# TK-BB-MD-06.net
KiCad netlist of a schematic drawn in EAGLE
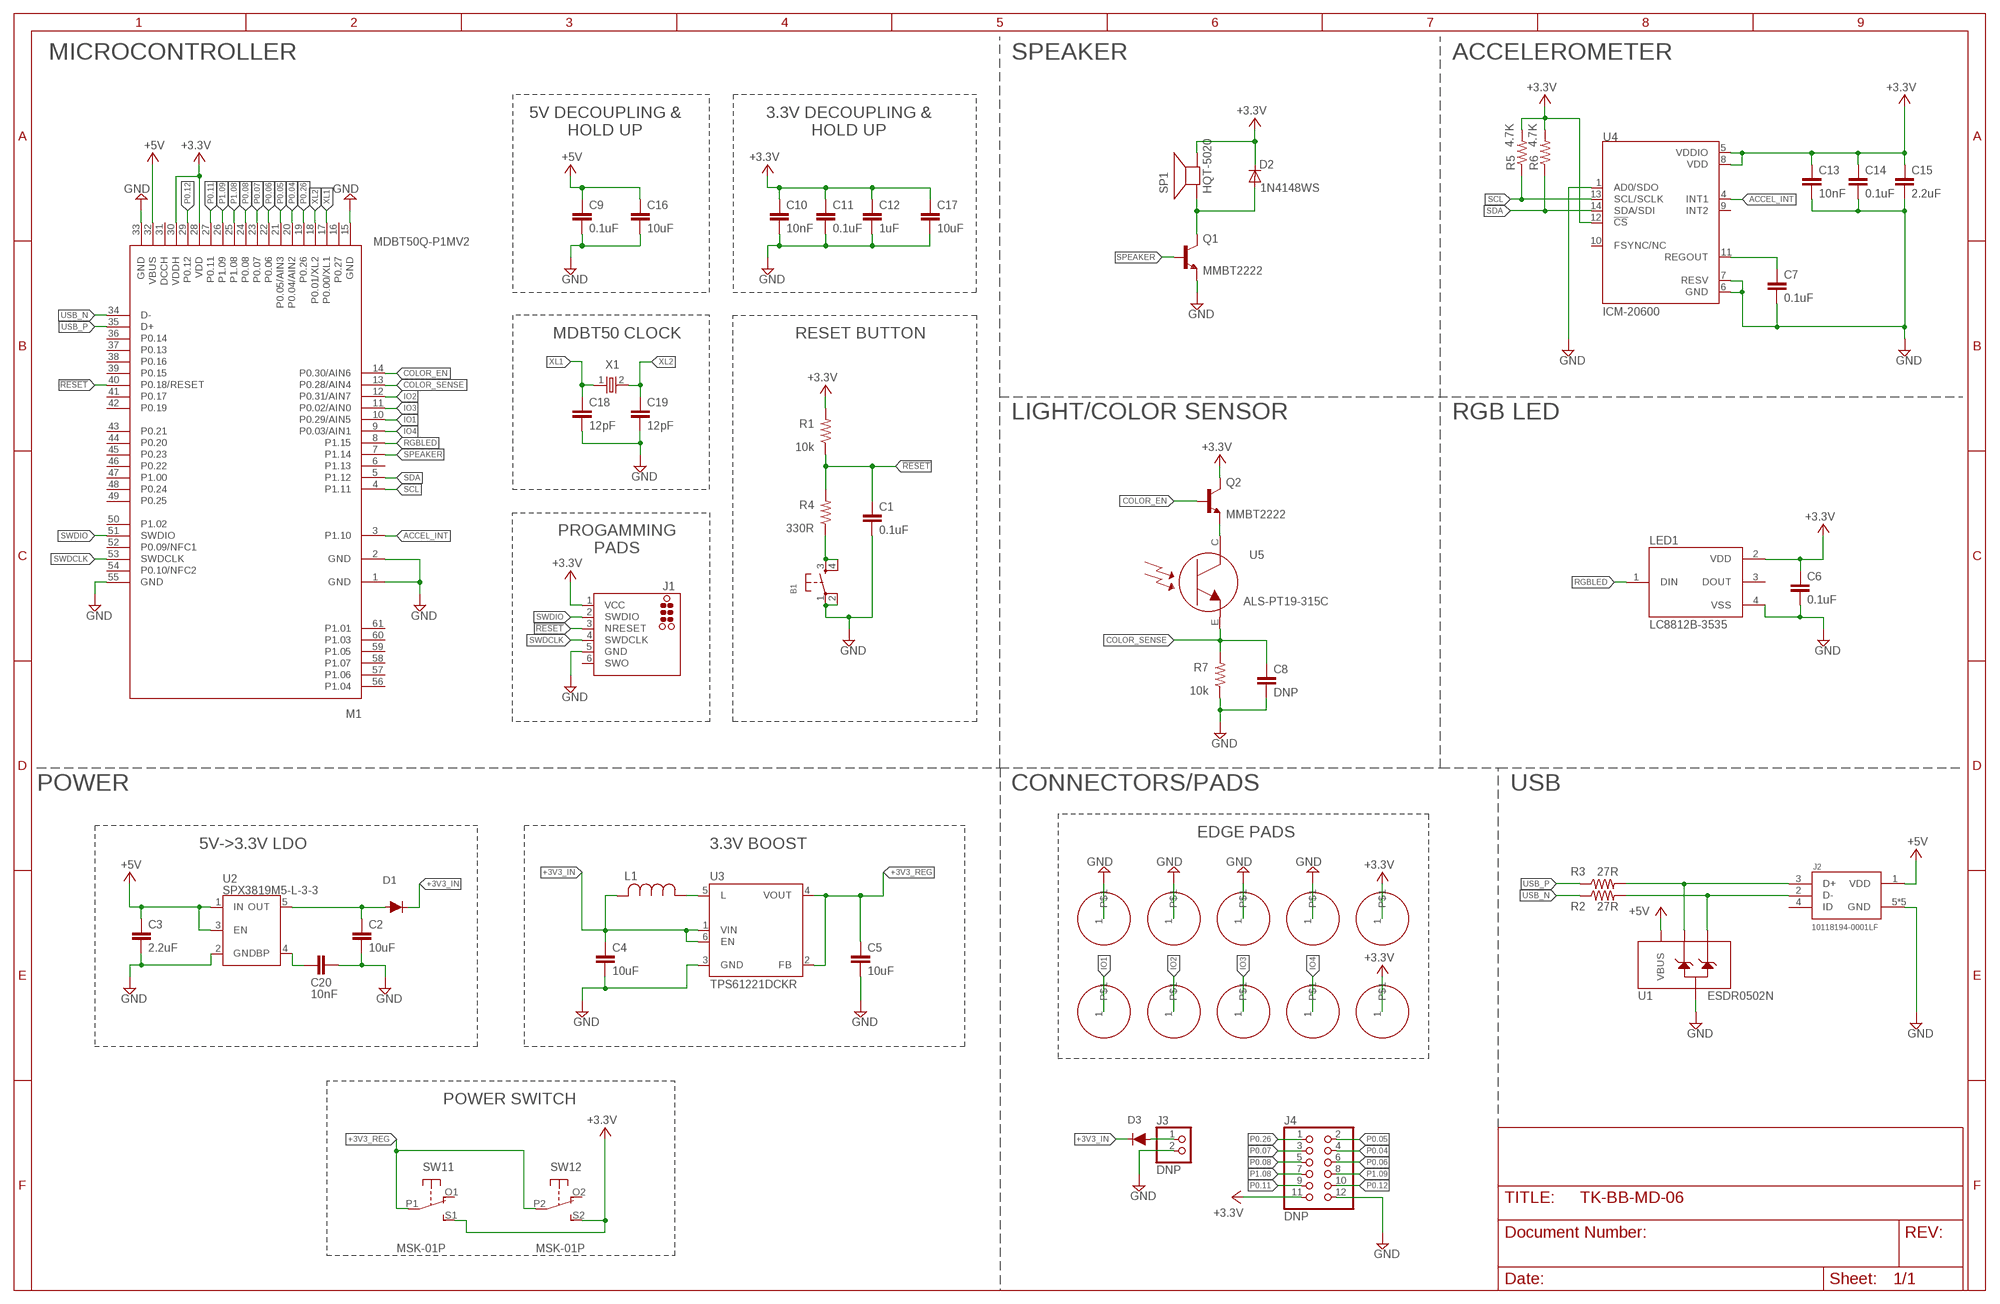
[diagram p0: schematic, sheet 1]

(export (version "E")
  (design (tool "Eeschema 10.0.6"))
  (components
    (comp (ref "B1")
      (value "KFC-A04-02(H3.8)")
      (footprint "eagle-import:KFC-AO4-02")
      (fields (field (name "MANUFACTURER") "Yeuqing City Ouke Electronics"))
      (libsource (lib "eagle-import") (part "BUTTON_SMT_KFC-A04-02_3.8MMH"))
    )
    (comp (ref "C1")
      (value "0.1uF")
      (footprint "eagle-import:0402")
      (fields
        (field (name "MANUFACTURER") "Yageo")
        (field (name "MANUFACTURER_PART_NUMBER") "CC0402KRX7R6BB104")
      )
      (libsource (lib "eagle-import") (part "C_0402_0.1UF_10V"))
    )
    (comp (ref "C2")
      (value "10uF")
      (footprint "eagle-import:0402")
      (fields
        (field (name "MANUFACTURER") "Samsung")
        (field (name "MANUFACTURER_PART_NUMBER") "CL05A106MP8NUB8")
      )
      (libsource (lib "eagle-import") (part "C_0402_10UF_10V"))
    )
    (comp (ref "C3")
      (value "2.2uF")
      (footprint "eagle-import:0402")
      (fields
        (field (name "MANUFACTURER") "Taiyo Yuden")
        (field (name "MANUFACTURER_PART_NUMBER") "LMK105BJ225MV-F")
      )
      (libsource (lib "eagle-import") (part "C_0402_2.2UF_10V"))
    )
    (comp (ref "C4")
      (value "10uF")
      (footprint "eagle-import:0402")
      (fields
        (field (name "MANUFACTURER") "Samsung")
        (field (name "MANUFACTURER_PART_NUMBER") "CL05A106MP8NUB8")
      )
      (libsource (lib "eagle-import") (part "C_0402_10UF_10V"))
    )
    (comp (ref "C5")
      (value "10uF")
      (footprint "eagle-import:0402")
      (fields
        (field (name "MANUFACTURER") "Samsung")
        (field (name "MANUFACTURER_PART_NUMBER") "CL05A106MP8NUB8")
      )
      (libsource (lib "eagle-import") (part "C_0402_10UF_10V"))
    )
    (comp (ref "C6")
      (value "0.1uF")
      (footprint "eagle-import:0402")
      (fields
        (field (name "MANUFACTURER") "Yageo")
        (field (name "MANUFACTURER_PART_NUMBER") "CC0402KRX7R6BB104")
      )
      (libsource (lib "eagle-import") (part "C_0402_0.1UF_10V"))
    )
    (comp (ref "C7")
      (value "0.1uF")
      (footprint "eagle-import:0402")
      (fields
        (field (name "MANUFACTURER") "Yageo")
        (field (name "MANUFACTURER_PART_NUMBER") "CC0402KRX7R6BB104")
      )
      (libsource (lib "eagle-import") (part "C_0402_0.1UF_10V"))
    )
    (comp (ref "C8")
      (value "DNP")
      (footprint "eagle-import:0402")
      (libsource (lib "eagle-import") (part "C_0402_DNP"))
    )
    (comp (ref "C9")
      (value "0.1uF")
      (footprint "eagle-import:0402")
      (fields
        (field (name "MANUFACTURER") "Yageo")
        (field (name "MANUFACTURER_PART_NUMBER") "CC0402KRX7R6BB104")
      )
      (libsource (lib "eagle-import") (part "C_0402_0.1UF_10V"))
    )
    (comp (ref "C10")
      (value "10nF")
      (footprint "eagle-import:0402")
      (fields
        (field (name "MANUFACTURER") "Yageo")
        (field (name "MANUFACTURER_PART_NUMBER") "C0402C103K8RACTU")
      )
      (libsource (lib "eagle-import") (part "C_0402_10NF_10V"))
    )
    (comp (ref "C11")
      (value "0.1uF")
      (footprint "eagle-import:0402")
      (fields
        (field (name "MANUFACTURER") "Yageo")
        (field (name "MANUFACTURER_PART_NUMBER") "CC0402KRX7R6BB104")
      )
      (libsource (lib "eagle-import") (part "C_0402_0.1UF_10V"))
    )
    (comp (ref "C12")
      (value "1uF")
      (footprint "eagle-import:0402")
      (fields
        (field (name "MANUFACTURER") "Yageo")
        (field (name "MANUFACTURER_PART_NUMBER") "CC0402KRX5R6BB105")
      )
      (libsource (lib "eagle-import") (part "C_0402_1UF_10V"))
    )
    (comp (ref "C13")
      (value "10nF")
      (footprint "eagle-import:0402")
      (fields
        (field (name "MANUFACTURER") "Yageo")
        (field (name "MANUFACTURER_PART_NUMBER") "C0402C103K8RACTU")
      )
      (libsource (lib "eagle-import") (part "C_0402_10NF_10V"))
    )
    (comp (ref "C14")
      (value "0.1uF")
      (footprint "eagle-import:0402")
      (fields
        (field (name "MANUFACTURER") "Yageo")
        (field (name "MANUFACTURER_PART_NUMBER") "CC0402KRX7R6BB104")
      )
      (libsource (lib "eagle-import") (part "C_0402_0.1UF_10V"))
    )
    (comp (ref "C15")
      (value "2.2uF")
      (footprint "eagle-import:0402")
      (fields
        (field (name "MANUFACTURER") "Taiyo Yuden")
        (field (name "MANUFACTURER_PART_NUMBER") "LMK105BJ225MV-F")
      )
      (libsource (lib "eagle-import") (part "C_0402_2.2UF_10V"))
    )
    (comp (ref "C16")
      (value "10uF")
      (footprint "eagle-import:0402")
      (fields
        (field (name "MANUFACTURER") "Samsung")
        (field (name "MANUFACTURER_PART_NUMBER") "CL05A106MP8NUB8")
      )
      (libsource (lib "eagle-import") (part "C_0402_10UF_10V"))
    )
    (comp (ref "C17")
      (value "10uF")
      (footprint "eagle-import:0402")
      (fields
        (field (name "MANUFACTURER") "Samsung")
        (field (name "MANUFACTURER_PART_NUMBER") "CL05A106MP8NUB8")
      )
      (libsource (lib "eagle-import") (part "C_0402_10UF_10V"))
    )
    (comp (ref "C18")
      (value "12pF")
      (footprint "eagle-import:0402")
      (fields
        (field (name "MANUFACTURER") "TDK Corporation")
        (field (name "MANUFACTURER_PART_NUMBER") "CGA2B2C0G1H120J050BA")
      )
      (libsource (lib "eagle-import") (part "C_0402_12PF_50V"))
    )
    (comp (ref "C19")
      (value "12pF")
      (footprint "eagle-import:0402")
      (fields
        (field (name "MANUFACTURER") "TDK Corporation")
        (field (name "MANUFACTURER_PART_NUMBER") "CGA2B2C0G1H120J050BA")
      )
      (libsource (lib "eagle-import") (part "C_0402_12PF_50V"))
    )
    (comp (ref "C20")
      (value "10nF")
      (footprint "eagle-import:0402")
      (fields
        (field (name "MANUFACTURER") "Yageo")
        (field (name "MANUFACTURER_PART_NUMBER") "C0402C103K8RACTU")
      )
      (libsource (lib "eagle-import") (part "C_0402_10NF_10V"))
    )
    (comp (ref "D1")
      (value "NSR0320MW2T1G")
      (footprint "eagle-import:SOD323")
      (fields (field (name "MANUFACTURER") "ON Semiconductor"))
      (libsource (lib "eagle-import") (part "DIODE_SCHOTTKY_NSR0320MW2T1G"))
    )
    (comp (ref "D2")
      (value "1N4148WS")
      (footprint "eagle-import:SOD-323")
      (fields (field (name "MANUFACTURER") "ON Semiconductor"))
      (libsource (lib "eagle-import") (part "DIODESOD-323_1N148WS"))
    )
    (comp (ref "D3")
      (value "NSR0320MW2T1G")
      (footprint "eagle-import:SOD323")
      (fields (field (name "MANUFACTURER") "ON Semiconductor"))
      (libsource (lib "eagle-import") (part "DIODE_SCHOTTKY_NSR0320MW2T1G"))
    )
    (comp (ref "J1")
      (value "DNP")
      (footprint "eagle-import:TC2030-MCP-NL")
      (libsource (lib "eagle-import") (part "TC2030-MCP-NL"))
    )
    (comp (ref "J2")
      (value "10118194-0001LF")
      (footprint "eagle-import:10118194-0001LF")
      (fields (field (name "MANUFACTURER") "Amphenol"))
      (libsource (lib "eagle-import") (part "10118194-0001LF"))
    )
    (comp (ref "J3")
      (value "DNP")
      (footprint "eagle-import:1X02")
      (fields
        (field (name "MANUFACTURER") "Amphenol")
        (field (name "MANUFACTURER_PART_NUMBER") "68000-402HLF")
      )
      (libsource (lib "eagle-import") (part "PINHD-1X2"))
    )
    (comp (ref "J4")
      (value "DNP")
      (footprint "eagle-import:2X06")
      (fields
        (field (name "MANUFACTURER") "Amphenol")
        (field (name "MANUFACTURER_PART_NUMBER") "67997-412HLF")
      )
      (libsource (lib "eagle-import") (part "PINHD-2X6"))
    )
    (comp (ref "L1")
      (value "4.7uH")
      (footprint "eagle-import:SRN30104R7M_IND_BOURNS_SRN3010")
      (fields
        (field (name "MANUFACTURER") "Bourns Electronics")
        (field (name "MANUFACTURER_PART_NUMBER") "SRN30104R7M")
      )
      (libsource (lib "eagle-import") (part "SRN30104R7M_SRN3010-4R7M"))
    )
    (comp (ref "LED1")
      (value "LC8812B-3535")
      (footprint "eagle-import:LC8812B-3535")
      (libsource (lib "eagle-import") (part "SK6812MINI_LC8812B-3535"))
    )
    (comp (ref "M1")
      (value "MDBT50Q-P1MV2")
      (footprint "eagle-import:MDBT50")
      (fields (field (name "MANUFACTURER") "Raytac"))
      (libsource (lib "eagle-import") (part "MDBT50Q-P1MV2"))
    )
    (comp (ref "P1")
      (value "BB_CHICKLET_PADS_ROUND")
      (footprint "eagle-import:BB_CHICKLET_PAD")
      (libsource (lib "eagle-import") (part "BB_CHICKLET_PADS_ROUND"))
    )
    (comp (ref "P2")
      (value "BB_CHICKLET_PADS_ROUND")
      (footprint "eagle-import:BB_CHICKLET_PAD")
      (libsource (lib "eagle-import") (part "BB_CHICKLET_PADS_ROUND"))
    )
    (comp (ref "P3")
      (value "BB_CHICKLET_PADS_ROUND")
      (footprint "eagle-import:BB_CHICKLET_PAD")
      (libsource (lib "eagle-import") (part "BB_CHICKLET_PADS_ROUND"))
    )
    (comp (ref "P4")
      (value "BB_CHICKLET_PADS_ROUND")
      (footprint "eagle-import:BB_CHICKLET_PAD")
      (libsource (lib "eagle-import") (part "BB_CHICKLET_PADS_ROUND"))
    )
    (comp (ref "P5")
      (value "BB_CHICKLET_PADS_ROUND")
      (footprint "eagle-import:BB_CHICKLET_PAD")
      (libsource (lib "eagle-import") (part "BB_CHICKLET_PADS_ROUND"))
    )
    (comp (ref "P6")
      (value "BB_CHICKLET_PADS_ROUND")
      (footprint "eagle-import:BB_CHICKLET_PAD")
      (libsource (lib "eagle-import") (part "BB_CHICKLET_PADS_ROUND"))
    )
    (comp (ref "P7")
      (value "BB_CHICKLET_PADS_ROUND")
      (footprint "eagle-import:BB_CHICKLET_PAD")
      (libsource (lib "eagle-import") (part "BB_CHICKLET_PADS_ROUND"))
    )
    (comp (ref "P8")
      (value "BB_CHICKLET_PADS_ROUND")
      (footprint "eagle-import:BB_CHICKLET_PAD")
      (libsource (lib "eagle-import") (part "BB_CHICKLET_PADS_ROUND"))
    )
    (comp (ref "P9")
      (value "BB_CHICKLET_PADS_ROUND")
      (footprint "eagle-import:BB_CHICKLET_PAD")
      (libsource (lib "eagle-import") (part "BB_CHICKLET_PADS_ROUND"))
    )
    (comp (ref "P10")
      (value "BB_CHICKLET_PADS_ROUND")
      (footprint "eagle-import:BB_CHICKLET_PAD")
      (libsource (lib "eagle-import") (part "BB_CHICKLET_PADS_ROUND"))
    )
    (comp (ref "Q1")
      (value "MMBT2222")
      (footprint "eagle-import:SOT23-WIDE")
      (fields
        (field (name "MANUFACTURER") "ON Semiconductor")
        (field (name "MANUFACTURER_PART_NUMBER") "MMBT2222LT1G")
      )
      (libsource (lib "eagle-import") (part "TRANSISTOR_NPN_WIDE_MMBT2222"))
    )
    (comp (ref "Q2")
      (value "MMBT2222")
      (footprint "eagle-import:SOT23-WIDE")
      (fields
        (field (name "MANUFACTURER") "ON Semiconductor")
        (field (name "MANUFACTURER_PART_NUMBER") "MMBT2222LT1G")
      )
      (libsource (lib "eagle-import") (part "TRANSISTOR_NPN_WIDE_MMBT2222"))
    )
    (comp (ref "R1")
      (value "10k")
      (footprint "eagle-import:0402")
      (fields
        (field (name "MANUFACTURER") "Yageo")
        (field (name "MANUFACTURER_PART_NUMBER") "RC0402JR-0710KL")
      )
      (libsource (lib "eagle-import") (part "R_0402_10K_0.0625W"))
    )
    (comp (ref "R2")
      (value "27R")
      (footprint "eagle-import:0402")
      (fields
        (field (name "MANUFACTURER") "Yageo")
        (field (name "MANUFACTURER_PART_NUMBER") "AC0402FR-0727RL")
      )
      (libsource (lib "eagle-import") (part "R_0402_27R_0.0625W"))
    )
    (comp (ref "R3")
      (value "27R")
      (footprint "eagle-import:0402")
      (fields
        (field (name "MANUFACTURER") "Yageo")
        (field (name "MANUFACTURER_PART_NUMBER") "AC0402FR-0727RL")
      )
      (libsource (lib "eagle-import") (part "R_0402_27R_0.0625W"))
    )
    (comp (ref "R4")
      (value "330R")
      (footprint "eagle-import:0402")
      (fields
        (field (name "MANUFACTURER") "Yageo")
        (field (name "MANUFACTURER_PART_NUMBER") "RC0402JR-07330RL")
      )
      (libsource (lib "eagle-import") (part "R_0402_330R_0.0625W"))
    )
    (comp (ref "R5")
      (value "4.7K")
      (footprint "eagle-import:0402")
      (fields
        (field (name "MANUFACTURER") "Yageo")
        (field (name "MANUFACTURER_PART_NUMBER") "RC0402JR-074K7L")
      )
      (libsource (lib "eagle-import") (part "R_0402_4.7K_0.0625W"))
    )
    (comp (ref "R6")
      (value "4.7K")
      (footprint "eagle-import:0402")
      (fields
        (field (name "MANUFACTURER") "Yageo")
        (field (name "MANUFACTURER_PART_NUMBER") "RC0402JR-074K7L")
      )
      (libsource (lib "eagle-import") (part "R_0402_4.7K_0.0625W"))
    )
    (comp (ref "R7")
      (value "10k")
      (footprint "eagle-import:0402")
      (fields
        (field (name "MANUFACTURER") "Panasonic")
        (field (name "MANUFACTURER_PART_NUMBER") "ERJ-2GEJ103X")
      )
      (libsource (lib "eagle-import") (part "R_0402_10K_0.1W"))
    )
    (comp (ref "SP1")
      (value "HQT-5020")
      (footprint "eagle-import:HQT-5020")
      (libsource (lib "eagle-import") (part "SPEAKER_HQT-5020"))
    )
    (comp (ref "SW1")
      (value "MSK-01P")
      (footprint "eagle-import:MSK-01P")
      (fields (field (name "MANUFACTURER") "Shenzen Gangyuan Microkey Technology"))
      (libsource (lib "eagle-import") (part "DPDT_MSK-01P"))
    )
    (comp (ref "U1")
      (value "ESDR0502N")
      (footprint "eagle-import:6-UFDFN")
      (fields
        (field (name "MANUFACTURER") "ON Semiconductor")
        (field (name "MANUFACTURER_PART_NUMBER") "ESDR0502NMUTBG")
      )
      (libsource (lib "eagle-import") (part "ESDR0502N"))
    )
    (comp (ref "U2")
      (value "SPX3819M5-L-3-3")
      (footprint "eagle-import:SOT23-5")
      (fields (field (name "MANUFACTURER") "MaxLinear"))
      (libsource (lib "eagle-import") (part "SPX3819_3.3V"))
    )
    (comp (ref "U3")
      (value "TPS61221DCKR")
      (footprint "eagle-import:SC70-6")
      (fields (field (name "MANUFACTURER") "Texas Instruments"))
      (libsource (lib "eagle-import") (part "TPS61221"))
    )
    (comp (ref "U4")
      (value "ICM-20600")
      (footprint "eagle-import:ICM-20600")
      (fields (field (name "MANUFACTURER") "TDK-InvenSense"))
      (libsource (lib "eagle-import") (part "ICM-20600"))
    )
    (comp (ref "U5")
      (value "ALS-PT19-315C")
      (footprint "eagle-import:ALS-PT19-315C")
      (fields
        (field (name "MANUFACTURER") "Everlight Electronics Co Ltd")
        (field (name "MANUFACTURER_PART_NUMBER") "ALS-PT19-315C/L177/TR8")
      )
      (libsource (lib "eagle-import") (part "ALS-PT19-315C"))
    )
    (comp (ref "X1")
      (value "32kHz 9pF")
      (footprint "eagle-import:XTAL_3215_N")
      (description "CRYSTAL 32.7680KHZ 9PF SMD")
      (fields
        (field (name "MANUFACTURER") "EPSON")
        (field (name "MANUFACTURER_PART_NUMBER") "FC-135 32.7680KA-AC0")
        (field (name "MANUFACTURER_1") "ECS Inc.")
        (field (name "MANUFACTURER_PART_NUMBER_1") "ECS-.327-9-34B-TR")
      )
      (libsource (lib "eagle-import") (part "XTAL_32KHZ_9PF"))
    )
  )
  (nets
    (net (code "1") (name "+3.3V") (class "Default")
      (node (ref "C10") (pin "1") (pinfunction "1_1") (pintype "passive"))
      (node (ref "C11") (pin "1") (pinfunction "1_1") (pintype "passive"))
      (node (ref "C12") (pin "1") (pinfunction "1_1") (pintype "passive"))
      (node (ref "C13") (pin "1") (pinfunction "1_1") (pintype "passive"))
      (node (ref "C14") (pin "1") (pinfunction "1_1") (pintype "passive"))
      (node (ref "C15") (pin "1") (pinfunction "1_1") (pintype "passive"))
      (node (ref "C17") (pin "1") (pinfunction "1_1") (pintype "passive"))
      (node (ref "C6") (pin "1") (pinfunction "1_1") (pintype "passive"))
      (node (ref "D2") (pin "C") (pinfunction "C_C") (pintype "passive"))
      (node (ref "J1") (pin "1") (pinfunction "VCC_1") (pintype "passive"))
      (node (ref "J4") (pin "11") (pinfunction "11_11") (pintype "passive"))
      (node (ref "LED1") (pin "2") (pinfunction "VDD_2") (pintype "power_in"))
      (node (ref "M1") (pin "28") (pinfunction "VDD_28") (pintype "bidirectional"))
      (node (ref "M1") (pin "30") (pinfunction "VDDH_30") (pintype "bidirectional"))
      (node (ref "P10") (pin "1") (pinfunction "P$1_1") (pintype "bidirectional"))
      (node (ref "P9") (pin "1") (pinfunction "P$1_1") (pintype "bidirectional"))
      (node (ref "Q2") (pin "3") (pinfunction "C_3") (pintype "passive"))
      (node (ref "R1") (pin "2") (pinfunction "2_2") (pintype "passive"))
      (node (ref "R5") (pin "2") (pinfunction "2_2") (pintype "passive"))
      (node (ref "R6") (pin "2") (pinfunction "2_2") (pintype "passive"))
      (node (ref "SP1") (pin "-") (pinfunction "-_-") (pintype "passive"))
      (node (ref "SW1") (pin "S1") (pinfunction "S_S1") (pintype "passive"))
      (node (ref "SW1") (pin "S2") (pinfunction "S_S2") (pintype "passive"))
      (node (ref "U4") (pin "12") (pinfunction "~{CS}_12") (pintype "input"))
      (node (ref "U4") (pin "5") (pinfunction "VDDIO_5") (pintype "power_in"))
      (node (ref "U4") (pin "8") (pinfunction "VDD_8") (pintype "power_in"))
    )
    (net (code "2") (name "+3V3_IN") (class "Default")
      (node (ref "C4") (pin "1") (pinfunction "1_1") (pintype "passive"))
      (node (ref "D1") (pin "1") (pinfunction "C_1") (pintype "bidirectional"))
      (node (ref "D3") (pin "1") (pinfunction "C_1") (pintype "bidirectional"))
      (node (ref "L1") (pin "2") (pinfunction "2_2") (pintype "passive"))
      (node (ref "U3") (pin "1") (pinfunction "VIN_1") (pintype "bidirectional"))
      (node (ref "U3") (pin "6") (pinfunction "EN_6") (pintype "bidirectional"))
    )
    (net (code "3") (name "+3V3_REG") (class "Default")
      (node (ref "C5") (pin "1") (pinfunction "1_1") (pintype "passive"))
      (node (ref "SW1") (pin "P1") (pinfunction "P_P1") (pintype "passive"))
      (node (ref "SW1") (pin "P2") (pinfunction "P_P2") (pintype "passive"))
      (node (ref "U3") (pin "2") (pinfunction "FB_2") (pintype "bidirectional"))
      (node (ref "U3") (pin "4") (pinfunction "VOUT_4") (pintype "bidirectional"))
    )
    (net (code "4") (name "+5V") (class "Default")
      (node (ref "C16") (pin "1") (pinfunction "1_1") (pintype "passive"))
      (node (ref "C3") (pin "1") (pinfunction "1_1") (pintype "passive"))
      (node (ref "C9") (pin "1") (pinfunction "1_1") (pintype "passive"))
      (node (ref "J2") (pin "1") (pinfunction "VDD_1") (pintype "power_in"))
      (node (ref "M1") (pin "32") (pinfunction "VBUS_32") (pintype "bidirectional"))
      (node (ref "U1") (pin "P$6") (pinfunction "VBUS_P$6") (pintype "bidirectional"))
      (node (ref "U2") (pin "1") (pinfunction "IN_1") (pintype "input"))
      (node (ref "U2") (pin "3") (pinfunction "EN_3") (pintype "input"))
    )
    (net (code "5") (name "/~{RESET}") (class "Default")
      (node (ref "C1") (pin "1") (pinfunction "1_1") (pintype "passive"))
      (node (ref "J1") (pin "3") (pinfunction "NRESET_3") (pintype "power_in"))
      (node (ref "M1") (pin "40") (pinfunction "P0.18/RESET_40") (pintype "bidirectional"))
      (node (ref "R1") (pin "1") (pinfunction "1_1") (pintype "passive"))
      (node (ref "R4") (pin "2") (pinfunction "2_2") (pintype "passive"))
    )
    (net (code "6") (name "ACCEL_INT") (class "Default")
      (node (ref "M1") (pin "3") (pinfunction "P1.10_3") (pintype "bidirectional"))
      (node (ref "U4") (pin "4") (pinfunction "INT1_4") (pintype "output"))
    )
    (net (code "7") (name "COLOR_EN") (class "Default")
      (node (ref "M1") (pin "14") (pinfunction "P0.30/AIN6_14") (pintype "bidirectional"))
      (node (ref "Q2") (pin "1") (pinfunction "B_1") (pintype "passive"))
    )
    (net (code "8") (name "COLOR_SENSE") (class "Default")
      (node (ref "C8") (pin "1") (pinfunction "1_1") (pintype "passive"))
      (node (ref "M1") (pin "13") (pinfunction "P0.28/AIN4_13") (pintype "bidirectional"))
      (node (ref "R7") (pin "2") (pinfunction "2_2") (pintype "passive"))
      (node (ref "U5") (pin "E") (pinfunction "E_E") (pintype "bidirectional"))
    )
    (net (code "9") (name "GND") (class "Default")
      (node (ref "B1") (pin "1") (pinfunction "P_1") (pintype "passive"))
      (node (ref "B1") (pin "2") (pinfunction "P1_2") (pintype "passive"))
      (node (ref "C1") (pin "2") (pinfunction "2_2") (pintype "passive"))
      (node (ref "C10") (pin "2") (pinfunction "2_2") (pintype "passive"))
      (node (ref "C11") (pin "2") (pinfunction "2_2") (pintype "passive"))
      (node (ref "C12") (pin "2") (pinfunction "2_2") (pintype "passive"))
      (node (ref "C13") (pin "2") (pinfunction "2_2") (pintype "passive"))
      (node (ref "C14") (pin "2") (pinfunction "2_2") (pintype "passive"))
      (node (ref "C15") (pin "2") (pinfunction "2_2") (pintype "passive"))
      (node (ref "C16") (pin "2") (pinfunction "2_2") (pintype "passive"))
      (node (ref "C17") (pin "2") (pinfunction "2_2") (pintype "passive"))
      (node (ref "C18") (pin "2") (pinfunction "2_2") (pintype "passive"))
      (node (ref "C19") (pin "2") (pinfunction "2_2") (pintype "passive"))
      (node (ref "C2") (pin "2") (pinfunction "2_2") (pintype "passive"))
      (node (ref "C20") (pin "2") (pinfunction "2_2") (pintype "passive"))
      (node (ref "C3") (pin "2") (pinfunction "2_2") (pintype "passive"))
      (node (ref "C4") (pin "2") (pinfunction "2_2") (pintype "passive"))
      (node (ref "C5") (pin "2") (pinfunction "2_2") (pintype "passive"))
      (node (ref "C6") (pin "2") (pinfunction "2_2") (pintype "passive"))
      (node (ref "C7") (pin "2") (pinfunction "2_2") (pintype "passive"))
      (node (ref "C8") (pin "2") (pinfunction "2_2") (pintype "passive"))
      (node (ref "C9") (pin "2") (pinfunction "2_2") (pintype "passive"))
      (node (ref "J1") (pin "5") (pinfunction "GND_5") (pintype "output"))
      (node (ref "J2") (pin "5") (pinfunction "GND_5") (pintype "power_in"))
      (node (ref "J2") (pin "P$6") (pinfunction "GND_P$6") (pintype "power_in"))
      (node (ref "J2") (pin "P$7") (pinfunction "GND_P$7") (pintype "power_in"))
      (node (ref "J2") (pin "P$8") (pinfunction "GND_P$8") (pintype "power_in"))
      (node (ref "J2") (pin "P$9") (pinfunction "GND_P$9") (pintype "power_in"))
      (node (ref "J3") (pin "2") (pinfunction "2_2") (pintype "passive"))
      (node (ref "J4") (pin "12") (pinfunction "12_12") (pintype "passive"))
      (node (ref "LED1") (pin "4") (pinfunction "VSS_4") (pintype "power_in"))
      (node (ref "M1") (pin "1") (pinfunction "GND_1") (pintype "bidirectional"))
      (node (ref "M1") (pin "15") (pinfunction "GND_15") (pintype "bidirectional"))
      (node (ref "M1") (pin "2") (pinfunction "GND_2") (pintype "bidirectional"))
      (node (ref "M1") (pin "33") (pinfunction "GND_33") (pintype "bidirectional"))
      (node (ref "M1") (pin "55") (pinfunction "GND_55") (pintype "bidirectional"))
      (node (ref "P1") (pin "1") (pinfunction "P$1_1") (pintype "bidirectional"))
      (node (ref "P2") (pin "1") (pinfunction "P$1_1") (pintype "bidirectional"))
      (node (ref "P3") (pin "1") (pinfunction "P$1_1") (pintype "bidirectional"))
      (node (ref "P8") (pin "1") (pinfunction "P$1_1") (pintype "bidirectional"))
      (node (ref "Q1") (pin "2") (pinfunction "E_2") (pintype "passive"))
      (node (ref "R7") (pin "1") (pinfunction "1_1") (pintype "passive"))
      (node (ref "U1") (pin "P$1") (pinfunction "GND_P$1") (pintype "bidirectional"))
      (node (ref "U2") (pin "2") (pinfunction "GND_2") (pintype "input"))
      (node (ref "U3") (pin "3") (pinfunction "GND_3") (pintype "bidirectional"))
      (node (ref "U4") (pin "1") (pinfunction "AD0/SDO_1") (pintype "output"))
      (node (ref "U4") (pin "6") (pinfunction "GND_6") (pintype "power_in"))
      (node (ref "U4") (pin "7") (pinfunction "RESV_7") (pintype "power_in"))
    )
    (net (code "10") (name "IO1") (class "Default")
      (node (ref "M1") (pin "10") (pinfunction "P0.29/AIN5_10") (pintype "bidirectional"))
      (node (ref "P6") (pin "1") (pinfunction "P$1_1") (pintype "bidirectional"))
    )
    (net (code "11") (name "IO2") (class "Default")
      (node (ref "M1") (pin "12") (pinfunction "P0.31/AIN7_12") (pintype "bidirectional"))
      (node (ref "P4") (pin "1") (pinfunction "P$1_1") (pintype "bidirectional"))
    )
    (net (code "12") (name "IO3") (class "Default")
      (node (ref "M1") (pin "11") (pinfunction "P0.02/AIN0_11") (pintype "bidirectional"))
      (node (ref "P7") (pin "1") (pinfunction "P$1_1") (pintype "bidirectional"))
    )
    (net (code "13") (name "IO4") (class "Default")
      (node (ref "M1") (pin "9") (pinfunction "P0.03/AIN1_9") (pintype "bidirectional"))
      (node (ref "P5") (pin "1") (pinfunction "P$1_1") (pintype "bidirectional"))
    )
    (net (code "14") (name "Net-(B1-S)") (class "Default")
      (node (ref "B1") (pin "3") (pinfunction "S_3") (pintype "passive"))
      (node (ref "B1") (pin "4") (pinfunction "S1_4") (pintype "passive"))
      (node (ref "R4") (pin "1") (pinfunction "1_1") (pintype "passive"))
    )
    (net (code "15") (name "Net-(D1-A)") (class "Default")
      (node (ref "C2") (pin "1") (pinfunction "1_1") (pintype "passive"))
      (node (ref "D1") (pin "2") (pinfunction "A_2") (pintype "bidirectional"))
      (node (ref "U2") (pin "5") (pinfunction "OUT_5") (pintype "passive"))
    )
    (net (code "16") (name "Net-(D3-A)") (class "Default")
      (node (ref "D3") (pin "2") (pinfunction "A_2") (pintype "bidirectional"))
      (node (ref "J3") (pin "1") (pinfunction "1_1") (pintype "passive"))
    )
    (net (code "17") (name "Net-(J2-D+)") (class "Default")
      (node (ref "J2") (pin "3") (pinfunction "D+_3") (pintype "bidirectional"))
      (node (ref "R3") (pin "2") (pinfunction "2_2") (pintype "passive"))
      (node (ref "U1") (pin "P$2") (pinfunction "D+_P$2") (pintype "bidirectional"))
      (node (ref "U1") (pin "P$5") (pinfunction "D+_P$5") (pintype "bidirectional"))
    )
    (net (code "18") (name "Net-(J2-D-)") (class "Default")
      (node (ref "J2") (pin "2") (pinfunction "D-_2") (pintype "bidirectional"))
      (node (ref "R2") (pin "2") (pinfunction "2_2") (pintype "passive"))
      (node (ref "U1") (pin "P$3") (pinfunction "D-_P$3") (pintype "bidirectional"))
      (node (ref "U1") (pin "P$4") (pinfunction "D-_P$4") (pintype "bidirectional"))
    )
    (net (code "19") (name "Net-(Q1-C)") (class "Default")
      (node (ref "D2") (pin "A") (pinfunction "A_A") (pintype "passive"))
      (node (ref "Q1") (pin "3") (pinfunction "C_3") (pintype "passive"))
      (node (ref "SP1") (pin "+") (pinfunction "+_+") (pintype "passive"))
    )
    (net (code "20") (name "Net-(Q2-E)") (class "Default")
      (node (ref "Q2") (pin "2") (pinfunction "E_2") (pintype "passive"))
      (node (ref "U5") (pin "C") (pinfunction "C_C") (pintype "bidirectional"))
    )
    (net (code "21") (name "Net-(U2-BP)") (class "Default")
      (node (ref "C20") (pin "1") (pinfunction "1_1") (pintype "passive"))
      (node (ref "U2") (pin "4") (pinfunction "BP_4") (pintype "input"))
    )
    (net (code "22") (name "Net-(U3-L)") (class "Default")
      (node (ref "L1") (pin "1") (pinfunction "1_1") (pintype "passive"))
      (node (ref "U3") (pin "5") (pinfunction "L_5") (pintype "bidirectional"))
    )
    (net (code "23") (name "Net-(U4-REGOUT)") (class "Default")
      (node (ref "C7") (pin "1") (pinfunction "1_1") (pintype "passive"))
      (node (ref "U4") (pin "11") (pinfunction "REGOUT_11") (pintype "passive"))
    )
    (net (code "24") (name "P0.04") (class "Default")
      (node (ref "J4") (pin "4") (pinfunction "4_4") (pintype "passive"))
      (node (ref "M1") (pin "20") (pinfunction "P0.04/AIN2_20") (pintype "bidirectional"))
    )
    (net (code "25") (name "P0.05") (class "Default")
      (node (ref "J4") (pin "2") (pinfunction "2_2") (pintype "passive"))
      (node (ref "M1") (pin "21") (pinfunction "P0.05/AIN3_21") (pintype "bidirectional"))
    )
    (net (code "26") (name "P0.06") (class "Default")
      (node (ref "J4") (pin "6") (pinfunction "6_6") (pintype "passive"))
      (node (ref "M1") (pin "22") (pinfunction "P0.06_22") (pintype "bidirectional"))
    )
    (net (code "27") (name "P0.07") (class "Default")
      (node (ref "J4") (pin "3") (pinfunction "3_3") (pintype "passive"))
      (node (ref "M1") (pin "23") (pinfunction "P0.07_23") (pintype "bidirectional"))
    )
    (net (code "28") (name "P0.08") (class "Default")
      (node (ref "J4") (pin "5") (pinfunction "5_5") (pintype "passive"))
      (node (ref "M1") (pin "24") (pinfunction "P0.08_24") (pintype "bidirectional"))
    )
    (net (code "29") (name "P0.11") (class "Default")
      (node (ref "J4") (pin "9") (pinfunction "9_9") (pintype "passive"))
      (node (ref "M1") (pin "27") (pinfunction "P0.11_27") (pintype "bidirectional"))
    )
    (net (code "30") (name "P0.12") (class "Default")
      (node (ref "J4") (pin "10") (pinfunction "10_10") (pintype "passive"))
      (node (ref "M1") (pin "29") (pinfunction "P0.12_29") (pintype "bidirectional"))
    )
    (net (code "31") (name "P0.26") (class "Default")
      (node (ref "J4") (pin "1") (pinfunction "1_1") (pintype "passive"))
      (node (ref "M1") (pin "19") (pinfunction "P0.26_19") (pintype "bidirectional"))
    )
    (net (code "32") (name "P1.08") (class "Default")
      (node (ref "J4") (pin "7") (pinfunction "7_7") (pintype "passive"))
      (node (ref "M1") (pin "25") (pinfunction "P1.08_25") (pintype "bidirectional"))
    )
    (net (code "33") (name "P1.09") (class "Default")
      (node (ref "J4") (pin "8") (pinfunction "8_8") (pintype "passive"))
      (node (ref "M1") (pin "26") (pinfunction "P1.09_26") (pintype "bidirectional"))
    )
    (net (code "34") (name "RGBLED") (class "Default")
      (node (ref "LED1") (pin "1") (pinfunction "DIN_1") (pintype "input"))
      (node (ref "M1") (pin "8") (pinfunction "P1.15_8") (pintype "bidirectional"))
    )
    (net (code "35") (name "SCL") (class "Default")
      (node (ref "M1") (pin "4") (pinfunction "P1.11_4") (pintype "bidirectional"))
      (node (ref "R5") (pin "1") (pinfunction "1_1") (pintype "passive"))
      (node (ref "U4") (pin "13") (pinfunction "SCL/SCLK_13") (pintype "bidirectional"))
    )
    (net (code "36") (name "SDA") (class "Default")
      (node (ref "M1") (pin "5") (pinfunction "P1.12_5") (pintype "bidirectional"))
      (node (ref "R6") (pin "1") (pinfunction "1_1") (pintype "passive"))
      (node (ref "U4") (pin "14") (pinfunction "SDA/SDI_14") (pintype "bidirectional"))
    )
    (net (code "37") (name "SPEAKER") (class "Default")
      (node (ref "M1") (pin "7") (pinfunction "P1.14_7") (pintype "bidirectional"))
      (node (ref "Q1") (pin "1") (pinfunction "B_1") (pintype "passive"))
    )
    (net (code "38") (name "SWDCLK") (class "Default")
      (node (ref "J1") (pin "4") (pinfunction "SWDCLK_4") (pintype "bidirectional"))
      (node (ref "M1") (pin "53") (pinfunction "SWDCLK_53") (pintype "bidirectional"))
    )
    (net (code "39") (name "SWDIO") (class "Default")
      (node (ref "J1") (pin "2") (pinfunction "SWDIO_2") (pintype "power_in"))
      (node (ref "M1") (pin "51") (pinfunction "SWDIO_51") (pintype "bidirectional"))
    )
    (net (code "40") (name "USB_N") (class "Default")
      (node (ref "M1") (pin "34") (pinfunction "D-_34") (pintype "bidirectional"))
      (node (ref "R2") (pin "1") (pinfunction "1_1") (pintype "passive"))
    )
    (net (code "41") (name "USB_P") (class "Default")
      (node (ref "M1") (pin "35") (pinfunction "D+_35") (pintype "bidirectional"))
      (node (ref "R3") (pin "1") (pinfunction "1_1") (pintype "passive"))
    )
    (net (code "42") (name "XL1") (class "Default")
      (node (ref "C18") (pin "1") (pinfunction "1_1") (pintype "passive"))
      (node (ref "M1") (pin "17") (pinfunction "P0.00/XL1_17") (pintype "bidirectional"))
      (node (ref "X1") (pin "1") (pinfunction "1_1") (pintype "passive"))
    )
    (net (code "43") (name "XL2") (class "Default")
      (node (ref "C19") (pin "1") (pinfunction "1_1") (pintype "passive"))
      (node (ref "M1") (pin "18") (pinfunction "P0.01/XL2_18") (pintype "bidirectional"))
      (node (ref "X1") (pin "2") (pinfunction "2_2") (pintype "passive"))
    )
    (net (code "44") (name "unconnected-(J1-SWO-Pad6)") (class "Default")
      (node (ref "J1") (pin "6") (pinfunction "SWO_6") (pintype "bidirectional"))
    )
    (net (code "45") (name "unconnected-(J2-ID-Pad4)") (class "Default")
      (node (ref "J2") (pin "4") (pinfunction "ID_4") (pintype "passive"))
    )
    (net (code "46") (name "unconnected-(LED1-DOUT-Pad3)") (class "Default")
      (node (ref "LED1") (pin "3") (pinfunction "DOUT_3") (pintype "output"))
    )
    (net (code "47") (name "unconnected-(M1-DCCH-Pad31)") (class "Default")
      (node (ref "M1") (pin "31") (pinfunction "DCCH_31") (pintype "bidirectional"))
    )
    (net (code "48") (name "unconnected-(M1-P0.09{slash}NFC1-Pad52)") (class "Default")
      (node (ref "M1") (pin "52") (pinfunction "P0.09/NFC1_52") (pintype "bidirectional"))
    )
    (net (code "49") (name "unconnected-(M1-P0.10{slash}NFC2-Pad54)") (class "Default")
      (node (ref "M1") (pin "54") (pinfunction "P0.10/NFC2_54") (pintype "bidirectional"))
    )
    (net (code "50") (name "unconnected-(M1-P0.13-Pad37)") (class "Default")
      (node (ref "M1") (pin "37") (pinfunction "P0.13_37") (pintype "bidirectional"))
    )
    (net (code "51") (name "unconnected-(M1-P0.14-Pad36)") (class "Default")
      (node (ref "M1") (pin "36") (pinfunction "P0.14_36") (pintype "bidirectional"))
    )
    (net (code "52") (name "unconnected-(M1-P0.15-Pad39)") (class "Default")
      (node (ref "M1") (pin "39") (pinfunction "P0.15_39") (pintype "bidirectional"))
    )
    (net (code "53") (name "unconnected-(M1-P0.16-Pad38)") (class "Default")
      (node (ref "M1") (pin "38") (pinfunction "P0.16_38") (pintype "bidirectional"))
    )
    (net (code "54") (name "unconnected-(M1-P0.17-Pad41)") (class "Default")
      (node (ref "M1") (pin "41") (pinfunction "P0.17_41") (pintype "bidirectional"))
    )
    (net (code "55") (name "unconnected-(M1-P0.19-Pad42)") (class "Default")
      (node (ref "M1") (pin "42") (pinfunction "P0.19_42") (pintype "bidirectional"))
    )
    (net (code "56") (name "unconnected-(M1-P0.20-Pad44)") (class "Default")
      (node (ref "M1") (pin "44") (pinfunction "P0.20_44") (pintype "bidirectional"))
    )
    (net (code "57") (name "unconnected-(M1-P0.21-Pad43)") (class "Default")
      (node (ref "M1") (pin "43") (pinfunction "P0.21_43") (pintype "bidirectional"))
    )
    (net (code "58") (name "unconnected-(M1-P0.22-Pad46)") (class "Default")
      (node (ref "M1") (pin "46") (pinfunction "P0.22_46") (pintype "bidirectional"))
    )
    (net (code "59") (name "unconnected-(M1-P0.23-Pad45)") (class "Default")
      (node (ref "M1") (pin "45") (pinfunction "P0.23_45") (pintype "bidirectional"))
    )
    (net (code "60") (name "unconnected-(M1-P0.24-Pad48)") (class "Default")
      (node (ref "M1") (pin "48") (pinfunction "P0.24_48") (pintype "bidirectional"))
    )
    (net (code "61") (name "unconnected-(M1-P0.25-Pad49)") (class "Default")
      (node (ref "M1") (pin "49") (pinfunction "P0.25_49") (pintype "bidirectional"))
    )
    (net (code "62") (name "unconnected-(M1-P0.27-Pad16)") (class "Default")
      (node (ref "M1") (pin "16") (pinfunction "P0.27_16") (pintype "bidirectional"))
    )
    (net (code "63") (name "unconnected-(M1-P1.00-Pad47)") (class "Default")
      (node (ref "M1") (pin "47") (pinfunction "P1.00_47") (pintype "bidirectional"))
    )
    (net (code "64") (name "unconnected-(M1-P1.01-Pad61)") (class "Default")
      (node (ref "M1") (pin "61") (pinfunction "P1.01_61") (pintype "bidirectional"))
    )
    (net (code "65") (name "unconnected-(M1-P1.02-Pad50)") (class "Default")
      (node (ref "M1") (pin "50") (pinfunction "P1.02_50") (pintype "bidirectional"))
    )
    (net (code "66") (name "unconnected-(M1-P1.03-Pad60)") (class "Default")
      (node (ref "M1") (pin "60") (pinfunction "P1.03_60") (pintype "bidirectional"))
    )
    (net (code "67") (name "unconnected-(M1-P1.04-Pad56)") (class "Default")
      (node (ref "M1") (pin "56") (pinfunction "P1.04_56") (pintype "bidirectional"))
    )
    (net (code "68") (name "unconnected-(M1-P1.05-Pad59)") (class "Default")
      (node (ref "M1") (pin "59") (pinfunction "P1.05_59") (pintype "bidirectional"))
    )
    (net (code "69") (name "unconnected-(M1-P1.06-Pad57)") (class "Default")
      (node (ref "M1") (pin "57") (pinfunction "P1.06_57") (pintype "bidirectional"))
    )
    (net (code "70") (name "unconnected-(M1-P1.07-Pad58)") (class "Default")
      (node (ref "M1") (pin "58") (pinfunction "P1.07_58") (pintype "bidirectional"))
    )
    (net (code "71") (name "unconnected-(M1-P1.13-Pad6)") (class "Default")
      (node (ref "M1") (pin "6") (pinfunction "P1.13_6") (pintype "bidirectional"))
    )
    (net (code "72") (name "unconnected-(SW1A-O-PadO1)") (class "Default")
      (node (ref "SW1") (pin "O1") (pinfunction "O_O1") (pintype "passive"))
    )
    (net (code "73") (name "unconnected-(SW1B-O-PadO2)") (class "Default")
      (node (ref "SW1") (pin "O2") (pinfunction "O_O2") (pintype "passive"))
    )
    (net (code "74") (name "unconnected-(U4-FSYNC{slash}NC-Pad10)") (class "Default")
      (node (ref "U4") (pin "10") (pinfunction "FSYNC/NC_10") (pintype "input"))
    )
    (net (code "75") (name "unconnected-(U4-INT2-Pad9)") (class "Default")
      (node (ref "U4") (pin "9") (pinfunction "INT2_9") (pintype "output"))
    )
  )
)
